# 10_FPGA_HSIO_PWR.net
KiCad netlist of a schematic drawn in Altium Designer
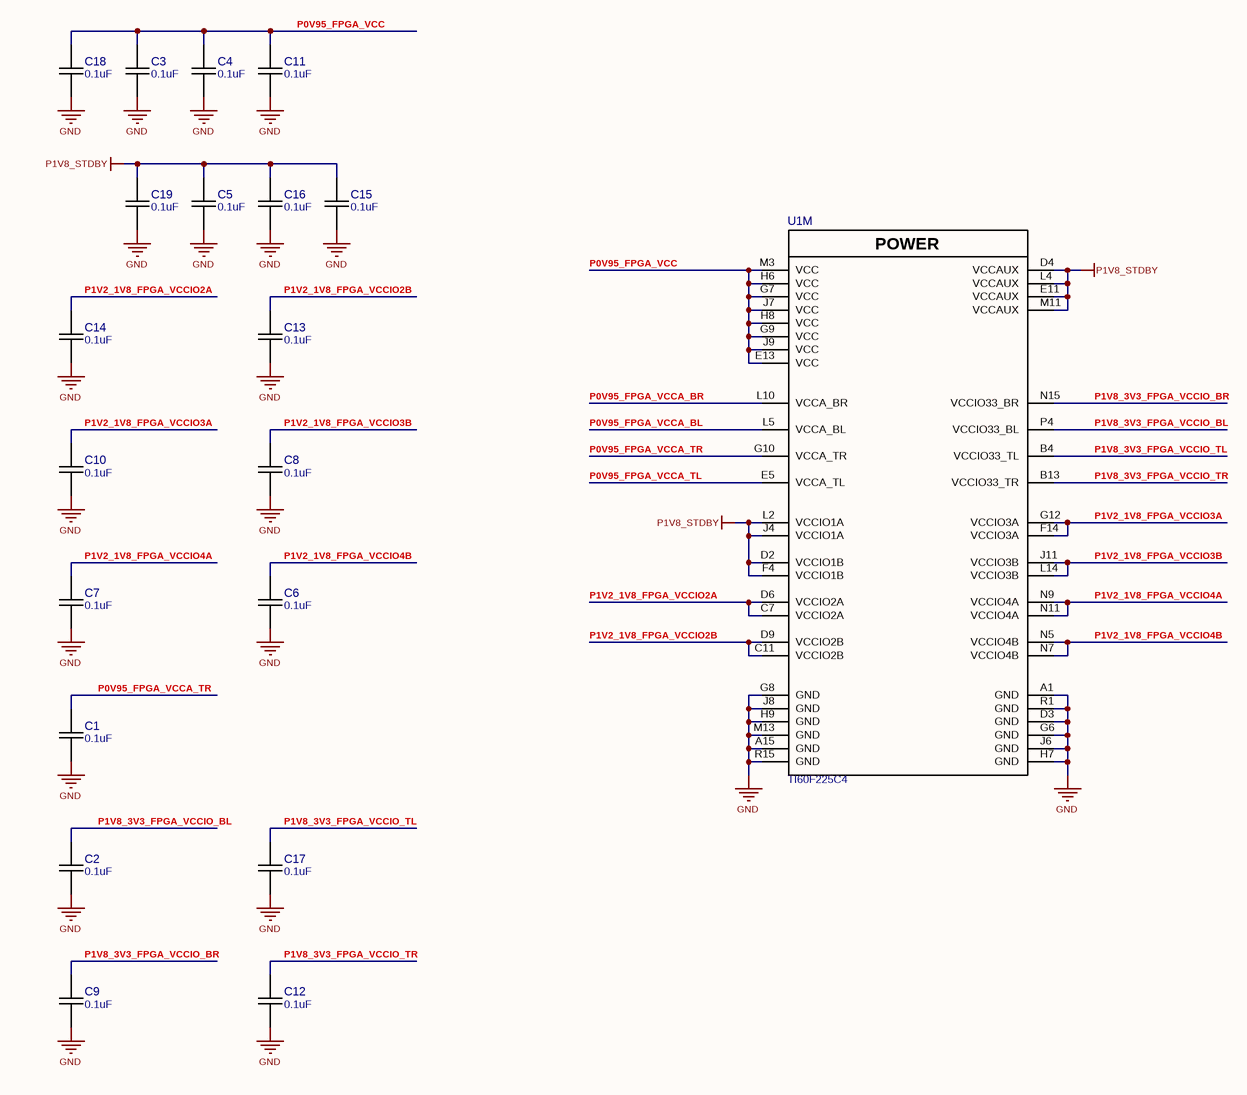
[diagram p0: 10_FPGA_HSIO_PWR.SchDoc]

(export (version "E")
  (design (tool "Eeschema 10.0.6"))
  (components
    (comp (ref "C1")
      (value "0.1uF")
      (footprint "CAPC1005X06N")
      (description "CAP CER 0.1UF 25V X7R 0402")
      (fields (field (name "PART NUMBER") "GRM155R71E104KE14J") (field (name "VOLTAGE") "25V"))
      (libsource (lib "Database") (part "Capacitor"))
    )
    (comp (ref "C2")
      (value "0.1uF")
      (footprint "CAPC1005X06N")
      (description "CAP CER 0.1UF 25V X7R 0402")
      (fields (field (name "PART NUMBER") "GRM155R71E104KE14J") (field (name "VOLTAGE") "25V"))
      (libsource (lib "Database") (part "Capacitor"))
    )
    (comp (ref "C3")
      (value "0.1uF")
      (footprint "CAPC1005X06N")
      (description "CAP CER 0.1UF 25V X7R 0402")
      (fields (field (name "PART NUMBER") "GRM155R71E104KE14J") (field (name "VOLTAGE") "25V"))
      (libsource (lib "Database") (part "Capacitor"))
    )
    (comp (ref "C4")
      (value "0.1uF")
      (footprint "CAPC1005X06N")
      (description "CAP CER 0.1UF 25V X7R 0402")
      (fields (field (name "PART NUMBER") "GRM155R71E104KE14J") (field (name "VOLTAGE") "25V"))
      (libsource (lib "Database") (part "Capacitor"))
    )
    (comp (ref "C5")
      (value "0.1uF")
      (footprint "CAPC1005X06N")
      (description "CAP CER 0.1UF 25V X7R 0402")
      (fields (field (name "PART NUMBER") "GRM155R71E104KE14J") (field (name "VOLTAGE") "25V"))
      (libsource (lib "Database") (part "Capacitor"))
    )
    (comp (ref "C6")
      (value "0.1uF")
      (footprint "CAPC1005X06N")
      (description "CAP CER 0.1UF 25V X7R 0402")
      (fields (field (name "PART NUMBER") "GRM155R71E104KE14J") (field (name "VOLTAGE") "25V"))
      (libsource (lib "Database") (part "Capacitor"))
    )
    (comp (ref "C7")
      (value "0.1uF")
      (footprint "CAPC1005X06N")
      (description "CAP CER 0.1UF 25V X7R 0402")
      (fields (field (name "PART NUMBER") "GRM155R71E104KE14J") (field (name "VOLTAGE") "25V"))
      (libsource (lib "Database") (part "Capacitor"))
    )
    (comp (ref "C8")
      (value "0.1uF")
      (footprint "CAPC1005X06N")
      (description "CAP CER 0.1UF 25V X7R 0402")
      (fields (field (name "PART NUMBER") "GRM155R71E104KE14J") (field (name "VOLTAGE") "25V"))
      (libsource (lib "Database") (part "Capacitor"))
    )
    (comp (ref "C9")
      (value "0.1uF")
      (footprint "CAPC1005X06N")
      (description "CAP CER 0.1UF 25V X7R 0402")
      (fields (field (name "PART NUMBER") "GRM155R71E104KE14J") (field (name "VOLTAGE") "25V"))
      (libsource (lib "Database") (part "Capacitor"))
    )
    (comp (ref "C10")
      (value "0.1uF")
      (footprint "CAPC1005X06N")
      (description "CAP CER 0.1UF 25V X7R 0402")
      (fields (field (name "PART NUMBER") "GRM155R71E104KE14J") (field (name "VOLTAGE") "25V"))
      (libsource (lib "Database") (part "Capacitor"))
    )
    (comp (ref "C11")
      (value "0.1uF")
      (footprint "CAPC1005X06N")
      (description "CAP CER 0.1UF 25V X7R 0402")
      (fields (field (name "PART NUMBER") "GRM155R71E104KE14J") (field (name "VOLTAGE") "25V"))
      (libsource (lib "Database") (part "Capacitor"))
    )
    (comp (ref "C12")
      (value "0.1uF")
      (footprint "CAPC1005X06N")
      (description "CAP CER 0.1UF 25V X7R 0402")
      (fields (field (name "PART NUMBER") "GRM155R71E104KE14J") (field (name "VOLTAGE") "25V"))
      (libsource (lib "Database") (part "Capacitor"))
    )
    (comp (ref "C13")
      (value "0.1uF")
      (footprint "CAPC1005X06N")
      (description "CAP CER 0.1UF 25V X7R 0402")
      (fields (field (name "PART NUMBER") "GRM155R71E104KE14J") (field (name "VOLTAGE") "25V"))
      (libsource (lib "Database") (part "Capacitor"))
    )
    (comp (ref "C14")
      (value "0.1uF")
      (footprint "CAPC1005X06N")
      (description "CAP CER 0.1UF 25V X7R 0402")
      (fields (field (name "PART NUMBER") "GRM155R71E104KE14J") (field (name "VOLTAGE") "25V"))
      (libsource (lib "Database") (part "Capacitor"))
    )
    (comp (ref "C15")
      (value "0.1uF")
      (footprint "CAPC1005X06N")
      (description "CAP CER 0.1UF 25V X7R 0402")
      (fields (field (name "PART NUMBER") "GRM155R71E104KE14J") (field (name "VOLTAGE") "25V"))
      (libsource (lib "Database") (part "Capacitor"))
    )
    (comp (ref "C16")
      (value "0.1uF")
      (footprint "CAPC1005X06N")
      (description "CAP CER 0.1UF 25V X7R 0402")
      (fields (field (name "PART NUMBER") "GRM155R71E104KE14J") (field (name "VOLTAGE") "25V"))
      (libsource (lib "Database") (part "Capacitor"))
    )
    (comp (ref "C17")
      (value "0.1uF")
      (footprint "CAPC1005X06N")
      (description "CAP CER 0.1UF 25V X7R 0402")
      (fields (field (name "PART NUMBER") "GRM155R71E104KE14J") (field (name "VOLTAGE") "25V"))
      (libsource (lib "Database") (part "Capacitor"))
    )
    (comp (ref "C18")
      (value "0.1uF")
      (footprint "CAPC1005X06N")
      (description "CAP CER 0.1UF 25V X7R 0402")
      (fields (field (name "PART NUMBER") "GRM155R71E104KE14J") (field (name "VOLTAGE") "25V"))
      (libsource (lib "Database") (part "Capacitor"))
    )
    (comp (ref "C19")
      (value "0.1uF")
      (footprint "CAPC1005X06N")
      (description "CAP CER 0.1UF 25V X7R 0402")
      (fields (field (name "PART NUMBER") "GRM155R71E104KE14J") (field (name "VOLTAGE") "25V"))
      (libsource (lib "Database") (part "Capacitor"))
    )
    (comp (ref "U1")
      (value "TI60F225C4")
      (footprint "BGA225C65P15X15_1000X1000X100")
      (description "FPGA TITAN 140HSIO 4PLL 225BGA")
      (libsource (lib "Database") (part "TI60F225"))
    )
  )
  (nets
    (net (code "1") (name "/P0V95_FPGA_VCC") (class "Default")
      (node (ref "C11") (pin "2") (pinfunction "2_2") (pintype "passive"))
      (node (ref "C18") (pin "2") (pinfunction "2_2") (pintype "passive"))
      (node (ref "C3") (pin "2") (pinfunction "2_2") (pintype "passive"))
      (node (ref "C4") (pin "2") (pinfunction "2_2") (pintype "passive"))
      (node (ref "U1") (pin "E13") (pinfunction "VCC_E13") (pintype "passive"))
      (node (ref "U1") (pin "G7") (pinfunction "VCC_G7") (pintype "passive"))
      (node (ref "U1") (pin "G9") (pinfunction "VCC_G9") (pintype "passive"))
      (node (ref "U1") (pin "H6") (pinfunction "VCC_H6") (pintype "passive"))
      (node (ref "U1") (pin "H8") (pinfunction "VCC_H8") (pintype "passive"))
      (node (ref "U1") (pin "J7") (pinfunction "VCC_J7") (pintype "passive"))
      (node (ref "U1") (pin "J9") (pinfunction "VCC_J9") (pintype "passive"))
      (node (ref "U1") (pin "M3") (pinfunction "VCC_M3") (pintype "passive"))
    )
    (net (code "2") (name "/P0V95_FPGA_VCCA_BL") (class "Default")
      (node (ref "U1") (pin "L5") (pinfunction "VCCA_BL_L5") (pintype "passive"))
    )
    (net (code "3") (name "/P0V95_FPGA_VCCA_BR") (class "Default")
      (node (ref "U1") (pin "L10") (pinfunction "VCCA_BR_L10") (pintype "passive"))
    )
    (net (code "4") (name "/P0V95_FPGA_VCCA_TL") (class "Default")
      (node (ref "U1") (pin "E5") (pinfunction "VCCA_TL_E5") (pintype "passive"))
    )
    (net (code "5") (name "/P0V95_FPGA_VCCA_TR") (class "Default")
      (node (ref "C1") (pin "2") (pinfunction "2_2") (pintype "passive"))
      (node (ref "U1") (pin "G10") (pinfunction "VCCA_TR_G10") (pintype "passive"))
    )
    (net (code "6") (name "/P1V2_1V8_FPGA_VCCIO2A") (class "Default")
      (node (ref "C14") (pin "2") (pinfunction "2_2") (pintype "passive"))
      (node (ref "U1") (pin "C7") (pinfunction "VCCIO2A_C7") (pintype "passive"))
      (node (ref "U1") (pin "D6") (pinfunction "VCCIO2A_D6") (pintype "passive"))
    )
    (net (code "7") (name "/P1V2_1V8_FPGA_VCCIO2B") (class "Default")
      (node (ref "C13") (pin "2") (pinfunction "2_2") (pintype "passive"))
      (node (ref "U1") (pin "C11") (pinfunction "VCCIO2B_C11") (pintype "passive"))
      (node (ref "U1") (pin "D9") (pinfunction "VCCIO2B_D9") (pintype "passive"))
    )
    (net (code "8") (name "/P1V2_1V8_FPGA_VCCIO3A") (class "Default")
      (node (ref "C10") (pin "2") (pinfunction "2_2") (pintype "passive"))
      (node (ref "U1") (pin "F14") (pinfunction "VCCIO3A_F14") (pintype "passive"))
      (node (ref "U1") (pin "G12") (pinfunction "VCCIO3A_G12") (pintype "passive"))
    )
    (net (code "9") (name "/P1V2_1V8_FPGA_VCCIO3B") (class "Default")
      (node (ref "C8") (pin "2") (pinfunction "2_2") (pintype "passive"))
      (node (ref "U1") (pin "J11") (pinfunction "VCCIO3B_J11") (pintype "passive"))
      (node (ref "U1") (pin "L14") (pinfunction "VCCIO3B_L14") (pintype "passive"))
    )
    (net (code "10") (name "/P1V2_1V8_FPGA_VCCIO4A") (class "Default")
      (node (ref "C7") (pin "2") (pinfunction "2_2") (pintype "passive"))
      (node (ref "U1") (pin "N11") (pinfunction "VCCIO4A_N11") (pintype "passive"))
      (node (ref "U1") (pin "N9") (pinfunction "VCCIO4A_N9") (pintype "passive"))
    )
    (net (code "11") (name "/P1V2_1V8_FPGA_VCCIO4B") (class "Default")
      (node (ref "C6") (pin "2") (pinfunction "2_2") (pintype "passive"))
      (node (ref "U1") (pin "N5") (pinfunction "VCCIO4B_N5") (pintype "passive"))
      (node (ref "U1") (pin "N7") (pinfunction "VCCIO4B_N7") (pintype "passive"))
    )
    (net (code "12") (name "/P1V8_3V3_FPGA_VCCIO_BL") (class "Default")
      (node (ref "C2") (pin "2") (pinfunction "2_2") (pintype "passive"))
      (node (ref "U1") (pin "P4") (pinfunction "VCCIO33_BL_P4") (pintype "passive"))
    )
    (net (code "13") (name "/P1V8_3V3_FPGA_VCCIO_BR") (class "Default")
      (node (ref "C9") (pin "2") (pinfunction "2_2") (pintype "passive"))
      (node (ref "U1") (pin "N15") (pinfunction "VCCIO33_BR_N15") (pintype "passive"))
    )
    (net (code "14") (name "/P1V8_3V3_FPGA_VCCIO_TL") (class "Default")
      (node (ref "C17") (pin "2") (pinfunction "2_2") (pintype "passive"))
      (node (ref "U1") (pin "B4") (pinfunction "VCCIO33_TL_B4") (pintype "passive"))
    )
    (net (code "15") (name "/P1V8_3V3_FPGA_VCCIO_TR") (class "Default")
      (node (ref "C12") (pin "2") (pinfunction "2_2") (pintype "passive"))
      (node (ref "U1") (pin "B13") (pinfunction "VCCIO33_TR_B13") (pintype "passive"))
    )
    (net (code "16") (name "GND") (class "Default")
      (node (ref "C1") (pin "1") (pinfunction "1_1") (pintype "passive"))
      (node (ref "C10") (pin "1") (pinfunction "1_1") (pintype "passive"))
      (node (ref "C11") (pin "1") (pinfunction "1_1") (pintype "passive"))
      (node (ref "C12") (pin "1") (pinfunction "1_1") (pintype "passive"))
      (node (ref "C13") (pin "1") (pinfunction "1_1") (pintype "passive"))
      (node (ref "C14") (pin "1") (pinfunction "1_1") (pintype "passive"))
      (node (ref "C15") (pin "1") (pinfunction "1_1") (pintype "passive"))
      (node (ref "C16") (pin "1") (pinfunction "1_1") (pintype "passive"))
      (node (ref "C17") (pin "1") (pinfunction "1_1") (pintype "passive"))
      (node (ref "C18") (pin "1") (pinfunction "1_1") (pintype "passive"))
      (node (ref "C19") (pin "1") (pinfunction "1_1") (pintype "passive"))
      (node (ref "C2") (pin "1") (pinfunction "1_1") (pintype "passive"))
      (node (ref "C3") (pin "1") (pinfunction "1_1") (pintype "passive"))
      (node (ref "C4") (pin "1") (pinfunction "1_1") (pintype "passive"))
      (node (ref "C5") (pin "1") (pinfunction "1_1") (pintype "passive"))
      (node (ref "C6") (pin "1") (pinfunction "1_1") (pintype "passive"))
      (node (ref "C7") (pin "1") (pinfunction "1_1") (pintype "passive"))
      (node (ref "C8") (pin "1") (pinfunction "1_1") (pintype "passive"))
      (node (ref "C9") (pin "1") (pinfunction "1_1") (pintype "passive"))
      (node (ref "U1") (pin "A1") (pinfunction "GND_A1") (pintype "passive"))
      (node (ref "U1") (pin "A15") (pinfunction "GND_A15") (pintype "passive"))
      (node (ref "U1") (pin "D3") (pinfunction "GND_D3") (pintype "passive"))
      (node (ref "U1") (pin "G6") (pinfunction "GND_G6") (pintype "passive"))
      (node (ref "U1") (pin "G8") (pinfunction "GND_G8") (pintype "passive"))
      (node (ref "U1") (pin "H7") (pinfunction "GND_H7") (pintype "passive"))
      (node (ref "U1") (pin "H9") (pinfunction "GND_H9") (pintype "passive"))
      (node (ref "U1") (pin "J6") (pinfunction "GND_J6") (pintype "passive"))
      (node (ref "U1") (pin "J8") (pinfunction "GND_J8") (pintype "passive"))
      (node (ref "U1") (pin "M13") (pinfunction "GND_M13") (pintype "passive"))
      (node (ref "U1") (pin "R1") (pinfunction "GND_R1") (pintype "passive"))
      (node (ref "U1") (pin "R15") (pinfunction "GND_R15") (pintype "passive"))
    )
    (net (code "17") (name "P1V8_STDBY") (class "Default")
      (node (ref "C15") (pin "2") (pinfunction "2_2") (pintype "passive"))
      (node (ref "C16") (pin "2") (pinfunction "2_2") (pintype "passive"))
      (node (ref "C19") (pin "2") (pinfunction "2_2") (pintype "passive"))
      (node (ref "C5") (pin "2") (pinfunction "2_2") (pintype "passive"))
      (node (ref "U1") (pin "D2") (pinfunction "VCCIO1B_D2") (pintype "passive"))
      (node (ref "U1") (pin "D4") (pinfunction "VCCAUX_D4") (pintype "passive"))
      (node (ref "U1") (pin "E11") (pinfunction "VCCAUX_E11") (pintype "passive"))
      (node (ref "U1") (pin "F4") (pinfunction "VCCIO1B_F4") (pintype "passive"))
      (node (ref "U1") (pin "J4") (pinfunction "VCCIO1A_J4") (pintype "passive"))
      (node (ref "U1") (pin "L2") (pinfunction "VCCIO1A_L2") (pintype "passive"))
      (node (ref "U1") (pin "L4") (pinfunction "VCCAUX_L4") (pintype "passive"))
      (node (ref "U1") (pin "M11") (pinfunction "VCCAUX_M11") (pintype "passive"))
    )
  )
)
